# microradio-standard.net
KiCad netlist of a schematic drawn in EAGLE
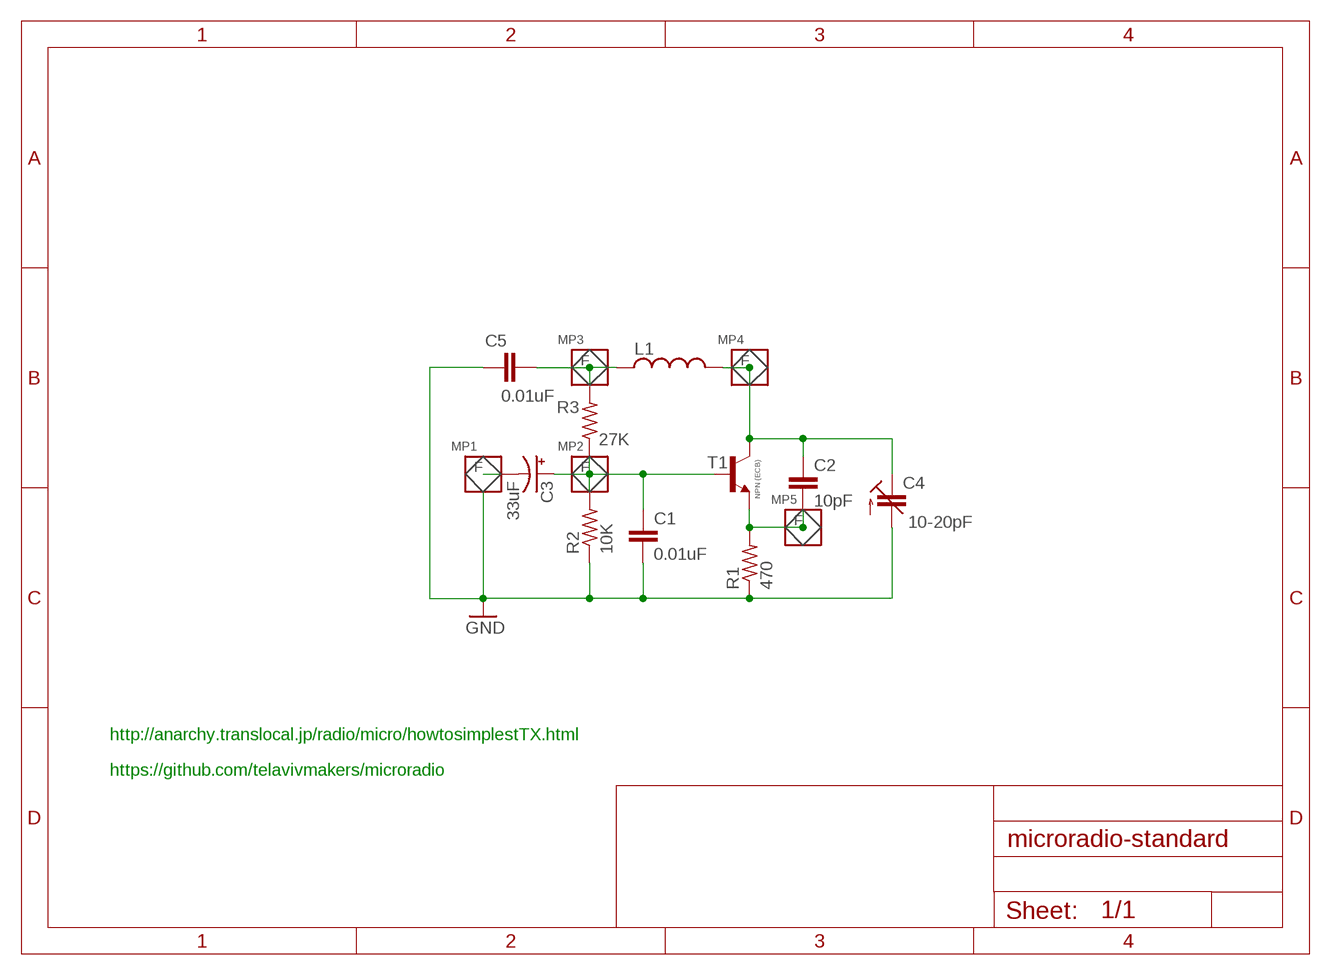
[diagram p0: schematic, sheet 1]

(export (version "E")
  (design (tool "Eeschema 10.0.6"))
  (components
    (comp (ref "C1")
      (value "0.01uF")
      (footprint "eagle-import:M1206")
      (libsource (lib "eagle-import") (part "C"))
    )
    (comp (ref "C2")
      (value "10pF")
      (footprint "eagle-import:C5B3")
      (libsource (lib "eagle-import") (part "C5/3"))
    )
    (comp (ref "C3")
      (value "33uF")
      (footprint "eagle-import:153CLV-0405")
      (libsource (lib "eagle-import") (part "CPOL-US153CLV-0405"))
    )
    (comp (ref "C4")
      (value "10-20pF")
      (footprint "eagle-import:3008")
      (libsource (lib "eagle-import") (part "C-TRIMM3008"))
    )
    (comp (ref "C5")
      (value "0.01uF")
      (footprint "eagle-import:M1206")
      (libsource (lib "eagle-import") (part "C"))
    )
    (comp (ref "L1")
      (value "L-US0204/5")
      (footprint "eagle-import:0204_5")
      (libsource (lib "eagle-import") (part "L-US0204/5"))
    )
    (comp (ref "MP1")
      (value "MICROSTRIPMI")
      (footprint "eagle-import:MICROSTRIP_5X5MM")
      (libsource (lib "eagle-import") (part "MICROSTRIPMI"))
    )
    (comp (ref "MP2")
      (value "MICROSTRIPMI")
      (footprint "eagle-import:MICROSTRIP_5X5MM")
      (libsource (lib "eagle-import") (part "MICROSTRIPMI"))
    )
    (comp (ref "MP3")
      (value "MICROSTRIPMI")
      (footprint "eagle-import:MICROSTRIP_5X5MM")
      (libsource (lib "eagle-import") (part "MICROSTRIPMI"))
    )
    (comp (ref "MP4")
      (value "MICROSTRIPMI")
      (footprint "eagle-import:MICROSTRIP_5X5MM")
      (libsource (lib "eagle-import") (part "MICROSTRIPMI"))
    )
    (comp (ref "MP5")
      (value "MICROSTRIPMI")
      (footprint "eagle-import:MICROSTRIP_5X5MM")
      (libsource (lib "eagle-import") (part "MICROSTRIPMI"))
    )
    (comp (ref "R1")
      (value "470")
      (footprint "eagle-import:R1206")
      (libsource (lib "eagle-import") (part "R-US_R1206"))
    )
    (comp (ref "R2")
      (value "10K")
      (footprint "eagle-import:R1206")
      (libsource (lib "eagle-import") (part "R-US_R1206"))
    )
    (comp (ref "R3")
      (value "27K")
      (footprint "eagle-import:R1206")
      (libsource (lib "eagle-import") (part "R-US_R1206"))
    )
    (comp (ref "T1")
      (value "NPN (ECB)")
      (footprint "eagle-import:TO92-BCE")
      (libsource (lib "eagle-import") (part "-NPN-TO92-BCE"))
    )
  )
  (nets
    (net (code "1") (name "GND") (class "Default")
      (node (ref "C1") (pin "2") (pinfunction "2_2") (pintype "passive"))
      (node (ref "C4") (pin "-") (pinfunction "A_-") (pintype "passive"))
      (node (ref "C5") (pin "2") (pinfunction "2_2") (pintype "passive"))
      (node (ref "R1") (pin "1") (pinfunction "1_1") (pintype "passive"))
      (node (ref "R2") (pin "1") (pinfunction "1_1") (pintype "passive"))
    )
    (net (code "2") (name "Net-(C4-E)") (class "Default")
      (node (ref "C2") (pin "1") (pinfunction "1_1") (pintype "passive"))
      (node (ref "C4") (pin "+") (pinfunction "E_+") (pintype "passive"))
      (node (ref "L1") (pin "2") (pinfunction "2_2") (pintype "passive"))
      (node (ref "MP4") (pin "F") (pinfunction "E_F") (pintype "bidirectional"))
      (node (ref "T1") (pin "C") (pinfunction "C_C") (pintype "passive"))
    )
    (net (code "3") (name "Net-(MP1-E)") (class "Default")
      (node (ref "C3") (pin "-") (pinfunction "-_-") (pintype "passive"))
      (node (ref "MP1") (pin "F") (pinfunction "E_F") (pintype "bidirectional"))
    )
    (net (code "4") (name "Net-(MP2-E)") (class "Default")
      (node (ref "C1") (pin "1") (pinfunction "1_1") (pintype "passive"))
      (node (ref "C3") (pin "+") (pinfunction "+_+") (pintype "passive"))
      (node (ref "MP2") (pin "F") (pinfunction "E_F") (pintype "bidirectional"))
      (node (ref "R2") (pin "2") (pinfunction "2_2") (pintype "passive"))
      (node (ref "R3") (pin "1") (pinfunction "1_1") (pintype "passive"))
      (node (ref "T1") (pin "B") (pinfunction "B_B") (pintype "passive"))
    )
    (net (code "5") (name "Net-(MP3-E)") (class "Default")
      (node (ref "C5") (pin "1") (pinfunction "1_1") (pintype "passive"))
      (node (ref "L1") (pin "1") (pinfunction "1_1") (pintype "passive"))
      (node (ref "MP3") (pin "F") (pinfunction "E_F") (pintype "bidirectional"))
      (node (ref "R3") (pin "2") (pinfunction "2_2") (pintype "passive"))
    )
    (net (code "6") (name "Net-(MP5-E)") (class "Default")
      (node (ref "C2") (pin "2") (pinfunction "2_2") (pintype "passive"))
      (node (ref "MP5") (pin "F") (pinfunction "E_F") (pintype "bidirectional"))
      (node (ref "R1") (pin "2") (pinfunction "2_2") (pintype "passive"))
      (node (ref "T1") (pin "E") (pinfunction "E_E") (pintype "passive"))
    )
  )
)
